# AFE_32_SUP.net
KiCad netlist of a schematic drawn in Altium Designer
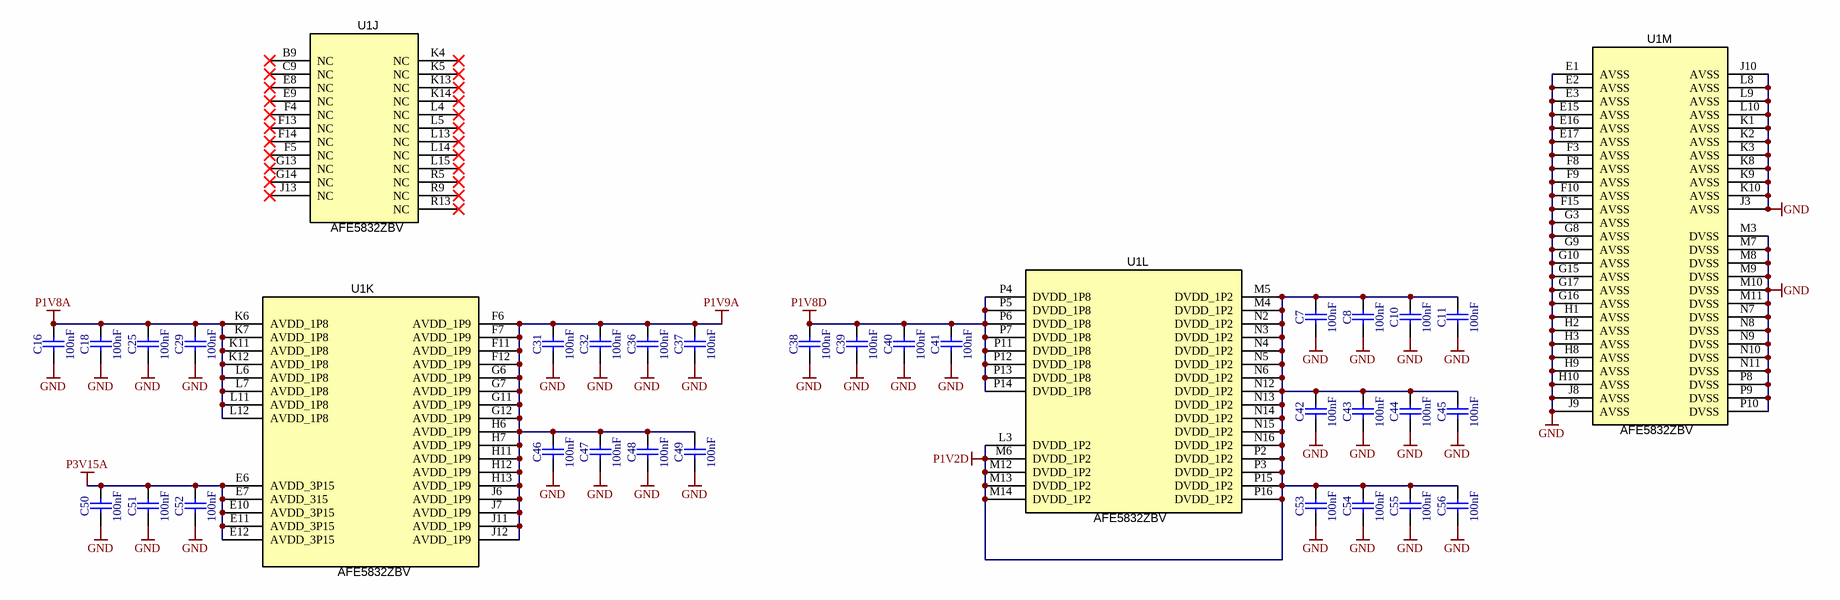
[diagram p0: AFE_32_SUP.SchDoc]

(export (version "E")
  (design (tool "Eeschema 10.0.6"))
  (components
    (comp (ref "C7")
      (value "100nF")
      (footprint "CAPC0603X33N")
      (description "Non-polarised capacitor")
      (fields
        (field (name "PART NUMBER") "CC0201_100NF_6.3V_10%_X7R")
        (field (name "VOLTAGE") "6.3V")
        (field (name "AUTHOR") "CERN DEM BC")
      )
      (libsource (lib "Capacitors") (part "Capacitor - non polarized"))
    )
    (comp (ref "C8")
      (value "100nF")
      (footprint "CAPC0603X33N")
      (description "Non-polarised capacitor")
      (fields
        (field (name "PART NUMBER") "CC0201_100NF_6.3V_10%_X7R")
        (field (name "VOLTAGE") "6.3V")
        (field (name "AUTHOR") "CERN DEM BC")
      )
      (libsource (lib "Capacitors") (part "Capacitor - non polarized"))
    )
    (comp (ref "C10")
      (value "100nF")
      (footprint "CAPC0603X33N")
      (description "Non-polarised capacitor")
      (fields
        (field (name "PART NUMBER") "CC0201_100NF_6.3V_10%_X7R")
        (field (name "VOLTAGE") "6.3V")
        (field (name "AUTHOR") "CERN DEM BC")
      )
      (libsource (lib "Capacitors") (part "Capacitor - non polarized"))
    )
    (comp (ref "C11")
      (value "100nF")
      (footprint "CAPC0603X33N")
      (description "Non-polarised capacitor")
      (fields
        (field (name "PART NUMBER") "CC0201_100NF_6.3V_10%_X7R")
        (field (name "VOLTAGE") "6.3V")
        (field (name "AUTHOR") "CERN DEM BC")
      )
      (libsource (lib "Capacitors") (part "Capacitor - non polarized"))
    )
    (comp (ref "C16")
      (value "100nF")
      (footprint "CAPC0603X33N")
      (description "Non-polarised capacitor")
      (fields
        (field (name "PART NUMBER") "CC0201_100NF_6.3V_10%_X7R")
        (field (name "VOLTAGE") "6.3V")
        (field (name "AUTHOR") "CERN DEM BC")
      )
      (libsource (lib "Capacitors") (part "Capacitor - non polarized"))
    )
    (comp (ref "C18")
      (value "100nF")
      (footprint "CAPC0603X33N")
      (description "Non-polarised capacitor")
      (fields
        (field (name "PART NUMBER") "CC0201_100NF_6.3V_10%_X7R")
        (field (name "VOLTAGE") "6.3V")
        (field (name "AUTHOR") "CERN DEM BC")
      )
      (libsource (lib "Capacitors") (part "Capacitor - non polarized"))
    )
    (comp (ref "C25")
      (value "100nF")
      (footprint "CAPC0603X33N")
      (description "Non-polarised capacitor")
      (fields
        (field (name "PART NUMBER") "CC0201_100NF_6.3V_10%_X7R")
        (field (name "VOLTAGE") "6.3V")
        (field (name "AUTHOR") "CERN DEM BC")
      )
      (libsource (lib "Capacitors") (part "Capacitor - non polarized"))
    )
    (comp (ref "C29")
      (value "100nF")
      (footprint "CAPC0603X33N")
      (description "Non-polarised capacitor")
      (fields
        (field (name "PART NUMBER") "CC0201_100NF_6.3V_10%_X7R")
        (field (name "VOLTAGE") "6.3V")
        (field (name "AUTHOR") "CERN DEM BC")
      )
      (libsource (lib "Capacitors") (part "Capacitor - non polarized"))
    )
    (comp (ref "C31")
      (value "100nF")
      (footprint "CAPC0603X33N")
      (description "Non-polarised capacitor")
      (fields
        (field (name "PART NUMBER") "CC0201_100NF_6.3V_10%_X7R")
        (field (name "VOLTAGE") "6.3V")
        (field (name "AUTHOR") "CERN DEM BC")
      )
      (libsource (lib "Capacitors") (part "Capacitor - non polarized"))
    )
    (comp (ref "C32")
      (value "100nF")
      (footprint "CAPC0603X33N")
      (description "Non-polarised capacitor")
      (fields
        (field (name "PART NUMBER") "CC0201_100NF_6.3V_10%_X7R")
        (field (name "VOLTAGE") "6.3V")
        (field (name "AUTHOR") "CERN DEM BC")
      )
      (libsource (lib "Capacitors") (part "Capacitor - non polarized"))
    )
    (comp (ref "C36")
      (value "100nF")
      (footprint "CAPC0603X33N")
      (description "Non-polarised capacitor")
      (fields
        (field (name "PART NUMBER") "CC0201_100NF_6.3V_10%_X7R")
        (field (name "VOLTAGE") "6.3V")
        (field (name "AUTHOR") "CERN DEM BC")
      )
      (libsource (lib "Capacitors") (part "Capacitor - non polarized"))
    )
    (comp (ref "C37")
      (value "100nF")
      (footprint "CAPC0603X33N")
      (description "Non-polarised capacitor")
      (fields
        (field (name "PART NUMBER") "CC0201_100NF_6.3V_10%_X7R")
        (field (name "VOLTAGE") "6.3V")
        (field (name "AUTHOR") "CERN DEM BC")
      )
      (libsource (lib "Capacitors") (part "Capacitor - non polarized"))
    )
    (comp (ref "C38")
      (value "100nF")
      (footprint "CAPC0603X33N")
      (description "Non-polarised capacitor")
      (fields
        (field (name "PART NUMBER") "CC0201_100NF_6.3V_10%_X7R")
        (field (name "VOLTAGE") "6.3V")
        (field (name "AUTHOR") "CERN DEM BC")
      )
      (libsource (lib "Capacitors") (part "Capacitor - non polarized"))
    )
    (comp (ref "C39")
      (value "100nF")
      (footprint "CAPC0603X33N")
      (description "Non-polarised capacitor")
      (fields
        (field (name "PART NUMBER") "CC0201_100NF_6.3V_10%_X7R")
        (field (name "VOLTAGE") "6.3V")
        (field (name "AUTHOR") "CERN DEM BC")
      )
      (libsource (lib "Capacitors") (part "Capacitor - non polarized"))
    )
    (comp (ref "C40")
      (value "100nF")
      (footprint "CAPC0603X33N")
      (description "Non-polarised capacitor")
      (fields
        (field (name "PART NUMBER") "CC0201_100NF_6.3V_10%_X7R")
        (field (name "VOLTAGE") "6.3V")
        (field (name "AUTHOR") "CERN DEM BC")
      )
      (libsource (lib "Capacitors") (part "Capacitor - non polarized"))
    )
    (comp (ref "C41")
      (value "100nF")
      (footprint "CAPC0603X33N")
      (description "Non-polarised capacitor")
      (fields
        (field (name "PART NUMBER") "CC0201_100NF_6.3V_10%_X7R")
        (field (name "VOLTAGE") "6.3V")
        (field (name "AUTHOR") "CERN DEM BC")
      )
      (libsource (lib "Capacitors") (part "Capacitor - non polarized"))
    )
    (comp (ref "C42")
      (value "100nF")
      (footprint "CAPC0603X33N")
      (description "Non-polarised capacitor")
      (fields
        (field (name "PART NUMBER") "CC0201_100NF_6.3V_10%_X7R")
        (field (name "VOLTAGE") "6.3V")
        (field (name "AUTHOR") "CERN DEM BC")
      )
      (libsource (lib "Capacitors") (part "Capacitor - non polarized"))
    )
    (comp (ref "C43")
      (value "100nF")
      (footprint "CAPC0603X33N")
      (description "Non-polarised capacitor")
      (fields
        (field (name "PART NUMBER") "CC0201_100NF_6.3V_10%_X7R")
        (field (name "VOLTAGE") "6.3V")
        (field (name "AUTHOR") "CERN DEM BC")
      )
      (libsource (lib "Capacitors") (part "Capacitor - non polarized"))
    )
    (comp (ref "C44")
      (value "100nF")
      (footprint "CAPC0603X33N")
      (description "Non-polarised capacitor")
      (fields
        (field (name "PART NUMBER") "CC0201_100NF_6.3V_10%_X7R")
        (field (name "VOLTAGE") "6.3V")
        (field (name "AUTHOR") "CERN DEM BC")
      )
      (libsource (lib "Capacitors") (part "Capacitor - non polarized"))
    )
    (comp (ref "C45")
      (value "100nF")
      (footprint "CAPC0603X33N")
      (description "Non-polarised capacitor")
      (fields
        (field (name "PART NUMBER") "CC0201_100NF_6.3V_10%_X7R")
        (field (name "VOLTAGE") "6.3V")
        (field (name "AUTHOR") "CERN DEM BC")
      )
      (libsource (lib "Capacitors") (part "Capacitor - non polarized"))
    )
    (comp (ref "C46")
      (value "100nF")
      (footprint "CAPC0603X33N")
      (description "Non-polarised capacitor")
      (fields
        (field (name "PART NUMBER") "CC0201_100NF_6.3V_10%_X7R")
        (field (name "VOLTAGE") "6.3V")
        (field (name "AUTHOR") "CERN DEM BC")
      )
      (libsource (lib "Capacitors") (part "Capacitor - non polarized"))
    )
    (comp (ref "C47")
      (value "100nF")
      (footprint "CAPC0603X33N")
      (description "Non-polarised capacitor")
      (fields
        (field (name "PART NUMBER") "CC0201_100NF_6.3V_10%_X7R")
        (field (name "VOLTAGE") "6.3V")
        (field (name "AUTHOR") "CERN DEM BC")
      )
      (libsource (lib "Capacitors") (part "Capacitor - non polarized"))
    )
    (comp (ref "C48")
      (value "100nF")
      (footprint "CAPC0603X33N")
      (description "Non-polarised capacitor")
      (fields
        (field (name "PART NUMBER") "CC0201_100NF_6.3V_10%_X7R")
        (field (name "VOLTAGE") "6.3V")
        (field (name "AUTHOR") "CERN DEM BC")
      )
      (libsource (lib "Capacitors") (part "Capacitor - non polarized"))
    )
    (comp (ref "C49")
      (value "100nF")
      (footprint "CAPC0603X33N")
      (description "Non-polarised capacitor")
      (fields
        (field (name "PART NUMBER") "CC0201_100NF_6.3V_10%_X7R")
        (field (name "VOLTAGE") "6.3V")
        (field (name "AUTHOR") "CERN DEM BC")
      )
      (libsource (lib "Capacitors") (part "Capacitor - non polarized"))
    )
    (comp (ref "C50")
      (value "100nF")
      (footprint "CAPC0603X33N")
      (description "Non-polarised capacitor")
      (fields
        (field (name "PART NUMBER") "CC0201_100NF_6.3V_10%_X7R")
        (field (name "VOLTAGE") "6.3V")
        (field (name "AUTHOR") "CERN DEM BC")
      )
      (libsource (lib "Capacitors") (part "Capacitor - non polarized"))
    )
    (comp (ref "C51")
      (value "100nF")
      (footprint "CAPC0603X33N")
      (description "Non-polarised capacitor")
      (fields
        (field (name "PART NUMBER") "CC0201_100NF_6.3V_10%_X7R")
        (field (name "VOLTAGE") "6.3V")
        (field (name "AUTHOR") "CERN DEM BC")
      )
      (libsource (lib "Capacitors") (part "Capacitor - non polarized"))
    )
    (comp (ref "C52")
      (value "100nF")
      (footprint "CAPC0603X33N")
      (description "Non-polarised capacitor")
      (fields
        (field (name "PART NUMBER") "CC0201_100NF_6.3V_10%_X7R")
        (field (name "VOLTAGE") "6.3V")
        (field (name "AUTHOR") "CERN DEM BC")
      )
      (libsource (lib "Capacitors") (part "Capacitor - non polarized"))
    )
    (comp (ref "C53")
      (value "100nF")
      (footprint "CAPC0603X33N")
      (description "Non-polarised capacitor")
      (fields
        (field (name "PART NUMBER") "CC0201_100NF_6.3V_10%_X7R")
        (field (name "VOLTAGE") "6.3V")
        (field (name "AUTHOR") "CERN DEM BC")
      )
      (libsource (lib "Capacitors") (part "Capacitor - non polarized"))
    )
    (comp (ref "C54")
      (value "100nF")
      (footprint "CAPC0603X33N")
      (description "Non-polarised capacitor")
      (fields
        (field (name "PART NUMBER") "CC0201_100NF_6.3V_10%_X7R")
        (field (name "VOLTAGE") "6.3V")
        (field (name "AUTHOR") "CERN DEM BC")
      )
      (libsource (lib "Capacitors") (part "Capacitor - non polarized"))
    )
    (comp (ref "C55")
      (value "100nF")
      (footprint "CAPC0603X33N")
      (description "Non-polarised capacitor")
      (fields
        (field (name "PART NUMBER") "CC0201_100NF_6.3V_10%_X7R")
        (field (name "VOLTAGE") "6.3V")
        (field (name "AUTHOR") "CERN DEM BC")
      )
      (libsource (lib "Capacitors") (part "Capacitor - non polarized"))
    )
    (comp (ref "C56")
      (value "100nF")
      (footprint "CAPC0603X33N")
      (description "Non-polarised capacitor")
      (fields
        (field (name "PART NUMBER") "CC0201_100NF_6.3V_10%_X7R")
        (field (name "VOLTAGE") "6.3V")
        (field (name "AUTHOR") "CERN DEM BC")
      )
      (libsource (lib "Capacitors") (part "Capacitor - non polarized"))
    )
    (comp (ref "U1")
      (value "AFE5832ZBV")
      (footprint "BGA289C80P17X17_1500X1500X140")
      (fields
        (field (name "MANUFACTURER") "Texas Instruments")
        (field (name "SYMBOLCREATOR") "Altium")
        (field (name "PUBLISHER") "Texas Instruments")
      )
      (libsource (lib "TI_Pre_RTM") (part "AFE58JD32ZBV"))
    )
  )
  (nets
    (net (code "1") (name "GND") (class "Default")
      (node (ref "C10") (pin "1") (pinfunction "1_1") (pintype "passive"))
      (node (ref "C11") (pin "1") (pinfunction "1_1") (pintype "passive"))
      (node (ref "C16") (pin "1") (pinfunction "1_1") (pintype "passive"))
      (node (ref "C18") (pin "1") (pinfunction "1_1") (pintype "passive"))
      (node (ref "C25") (pin "1") (pinfunction "1_1") (pintype "passive"))
      (node (ref "C29") (pin "1") (pinfunction "1_1") (pintype "passive"))
      (node (ref "C31") (pin "1") (pinfunction "1_1") (pintype "passive"))
      (node (ref "C32") (pin "1") (pinfunction "1_1") (pintype "passive"))
      (node (ref "C36") (pin "1") (pinfunction "1_1") (pintype "passive"))
      (node (ref "C37") (pin "1") (pinfunction "1_1") (pintype "passive"))
      (node (ref "C38") (pin "1") (pinfunction "1_1") (pintype "passive"))
      (node (ref "C39") (pin "1") (pinfunction "1_1") (pintype "passive"))
      (node (ref "C40") (pin "1") (pinfunction "1_1") (pintype "passive"))
      (node (ref "C41") (pin "1") (pinfunction "1_1") (pintype "passive"))
      (node (ref "C42") (pin "1") (pinfunction "1_1") (pintype "passive"))
      (node (ref "C43") (pin "1") (pinfunction "1_1") (pintype "passive"))
      (node (ref "C44") (pin "1") (pinfunction "1_1") (pintype "passive"))
      (node (ref "C45") (pin "1") (pinfunction "1_1") (pintype "passive"))
      (node (ref "C46") (pin "1") (pinfunction "1_1") (pintype "passive"))
      (node (ref "C47") (pin "1") (pinfunction "1_1") (pintype "passive"))
      (node (ref "C48") (pin "1") (pinfunction "1_1") (pintype "passive"))
      (node (ref "C49") (pin "1") (pinfunction "1_1") (pintype "passive"))
      (node (ref "C50") (pin "1") (pinfunction "1_1") (pintype "passive"))
      (node (ref "C51") (pin "1") (pinfunction "1_1") (pintype "passive"))
      (node (ref "C52") (pin "1") (pinfunction "1_1") (pintype "passive"))
      (node (ref "C53") (pin "1") (pinfunction "1_1") (pintype "passive"))
      (node (ref "C54") (pin "1") (pinfunction "1_1") (pintype "passive"))
      (node (ref "C55") (pin "1") (pinfunction "1_1") (pintype "passive"))
      (node (ref "C56") (pin "1") (pinfunction "1_1") (pintype "passive"))
      (node (ref "C7") (pin "1") (pinfunction "1_1") (pintype "passive"))
      (node (ref "C8") (pin "1") (pinfunction "1_1") (pintype "passive"))
      (node (ref "U1") (pin "E1") (pinfunction "AVSS_E1") (pintype "power_in"))
      (node (ref "U1") (pin "E15") (pinfunction "AVSS_E15") (pintype "power_in"))
      (node (ref "U1") (pin "E16") (pinfunction "AVSS_E16") (pintype "power_in"))
      (node (ref "U1") (pin "E17") (pinfunction "AVSS_E17") (pintype "power_in"))
      (node (ref "U1") (pin "E2") (pinfunction "AVSS_E2") (pintype "power_in"))
      (node (ref "U1") (pin "E3") (pinfunction "AVSS_E3") (pintype "power_in"))
      (node (ref "U1") (pin "F10") (pinfunction "AVSS_F10") (pintype "power_in"))
      (node (ref "U1") (pin "F15") (pinfunction "AVSS_F15") (pintype "power_in"))
      (node (ref "U1") (pin "F3") (pinfunction "AVSS_F3") (pintype "power_in"))
      (node (ref "U1") (pin "F8") (pinfunction "AVSS_F8") (pintype "power_in"))
      (node (ref "U1") (pin "F9") (pinfunction "AVSS_F9") (pintype "power_in"))
      (node (ref "U1") (pin "G10") (pinfunction "AVSS_G10") (pintype "power_in"))
      (node (ref "U1") (pin "G15") (pinfunction "AVSS_G15") (pintype "power_in"))
      (node (ref "U1") (pin "G16") (pinfunction "AVSS_G16") (pintype "power_in"))
      (node (ref "U1") (pin "G17") (pinfunction "AVSS_G17") (pintype "power_in"))
      (node (ref "U1") (pin "G3") (pinfunction "AVSS_G3") (pintype "power_in"))
      (node (ref "U1") (pin "G8") (pinfunction "AVSS_G8") (pintype "power_in"))
      (node (ref "U1") (pin "G9") (pinfunction "AVSS_G9") (pintype "power_in"))
      (node (ref "U1") (pin "H1") (pinfunction "AVSS_H1") (pintype "power_in"))
      (node (ref "U1") (pin "H10") (pinfunction "AVSS_H10") (pintype "power_in"))
      (node (ref "U1") (pin "H2") (pinfunction "AVSS_H2") (pintype "power_in"))
      (node (ref "U1") (pin "H3") (pinfunction "AVSS_H3") (pintype "power_in"))
      (node (ref "U1") (pin "H8") (pinfunction "AVSS_H8") (pintype "power_in"))
      (node (ref "U1") (pin "H9") (pinfunction "AVSS_H9") (pintype "power_in"))
      (node (ref "U1") (pin "J10") (pinfunction "AVSS_J10") (pintype "power_in"))
      (node (ref "U1") (pin "J3") (pinfunction "AVSS_J3") (pintype "power_in"))
      (node (ref "U1") (pin "J8") (pinfunction "AVSS_J8") (pintype "power_in"))
      (node (ref "U1") (pin "J9") (pinfunction "AVSS_J9") (pintype "power_in"))
      (node (ref "U1") (pin "K1") (pinfunction "AVSS_K1") (pintype "power_in"))
      (node (ref "U1") (pin "K10") (pinfunction "AVSS_K10") (pintype "power_in"))
      (node (ref "U1") (pin "K2") (pinfunction "AVSS_K2") (pintype "power_in"))
      (node (ref "U1") (pin "K3") (pinfunction "AVSS_K3") (pintype "power_in"))
      (node (ref "U1") (pin "K8") (pinfunction "AVSS_K8") (pintype "power_in"))
      (node (ref "U1") (pin "K9") (pinfunction "AVSS_K9") (pintype "power_in"))
      (node (ref "U1") (pin "L10") (pinfunction "AVSS_L10") (pintype "power_in"))
      (node (ref "U1") (pin "L8") (pinfunction "AVSS_L8") (pintype "power_in"))
      (node (ref "U1") (pin "L9") (pinfunction "AVSS_L9") (pintype "power_in"))
      (node (ref "U1") (pin "M10") (pinfunction "DVSS_M10") (pintype "power_in"))
      (node (ref "U1") (pin "M11") (pinfunction "DVSS_M11") (pintype "power_in"))
      (node (ref "U1") (pin "M3") (pinfunction "DVSS_M3") (pintype "power_in"))
      (node (ref "U1") (pin "M7") (pinfunction "DVSS_M7") (pintype "power_in"))
      (node (ref "U1") (pin "M8") (pinfunction "DVSS_M8") (pintype "power_in"))
      (node (ref "U1") (pin "M9") (pinfunction "DVSS_M9") (pintype "power_in"))
      (node (ref "U1") (pin "N10") (pinfunction "DVSS_N10") (pintype "power_in"))
      (node (ref "U1") (pin "N11") (pinfunction "DVSS_N11") (pintype "power_in"))
      (node (ref "U1") (pin "N7") (pinfunction "DVSS_N7") (pintype "power_in"))
      (node (ref "U1") (pin "N8") (pinfunction "DVSS_N8") (pintype "power_in"))
      (node (ref "U1") (pin "N9") (pinfunction "DVSS_N9") (pintype "power_in"))
      (node (ref "U1") (pin "P10") (pinfunction "DVSS_P10") (pintype "power_in"))
      (node (ref "U1") (pin "P8") (pinfunction "DVSS_P8") (pintype "power_in"))
      (node (ref "U1") (pin "P9") (pinfunction "DVSS_P9") (pintype "power_in"))
    )
    (net (code "2") (name "P1V2D") (class "Default")
      (node (ref "C10") (pin "2") (pinfunction "2_2") (pintype "passive"))
      (node (ref "C11") (pin "2") (pinfunction "2_2") (pintype "passive"))
      (node (ref "C42") (pin "2") (pinfunction "2_2") (pintype "passive"))
      (node (ref "C43") (pin "2") (pinfunction "2_2") (pintype "passive"))
      (node (ref "C44") (pin "2") (pinfunction "2_2") (pintype "passive"))
      (node (ref "C45") (pin "2") (pinfunction "2_2") (pintype "passive"))
      (node (ref "C53") (pin "2") (pinfunction "2_2") (pintype "passive"))
      (node (ref "C54") (pin "2") (pinfunction "2_2") (pintype "passive"))
      (node (ref "C55") (pin "2") (pinfunction "2_2") (pintype "passive"))
      (node (ref "C56") (pin "2") (pinfunction "2_2") (pintype "passive"))
      (node (ref "C7") (pin "2") (pinfunction "2_2") (pintype "passive"))
      (node (ref "C8") (pin "2") (pinfunction "2_2") (pintype "passive"))
      (node (ref "U1") (pin "L3") (pinfunction "DVDD_1P2_L3") (pintype "power_in"))
      (node (ref "U1") (pin "M12") (pinfunction "DVDD_1P2_M12") (pintype "power_in"))
      (node (ref "U1") (pin "M13") (pinfunction "DVDD_1P2_M13") (pintype "power_in"))
      (node (ref "U1") (pin "M14") (pinfunction "DVDD_1P2_M14") (pintype "power_in"))
      (node (ref "U1") (pin "M4") (pinfunction "DVDD_1P2_M4") (pintype "power_in"))
      (node (ref "U1") (pin "M5") (pinfunction "DVDD_1P2_M5") (pintype "power_in"))
      (node (ref "U1") (pin "M6") (pinfunction "DVDD_1P2_M6") (pintype "power_in"))
      (node (ref "U1") (pin "N12") (pinfunction "DVDD_1P2_N12") (pintype "power_in"))
      (node (ref "U1") (pin "N13") (pinfunction "DVDD_1P2_N13") (pintype "power_in"))
      (node (ref "U1") (pin "N14") (pinfunction "DVDD_1P2_N14") (pintype "power_in"))
      (node (ref "U1") (pin "N15") (pinfunction "DVDD_1P2_N15") (pintype "power_in"))
      (node (ref "U1") (pin "N16") (pinfunction "DVDD_1P2_N16") (pintype "power_in"))
      (node (ref "U1") (pin "N2") (pinfunction "DVDD_1P2_N2") (pintype "power_in"))
      (node (ref "U1") (pin "N3") (pinfunction "DVDD_1P2_N3") (pintype "power_in"))
      (node (ref "U1") (pin "N4") (pinfunction "DVDD_1P2_N4") (pintype "power_in"))
      (node (ref "U1") (pin "N5") (pinfunction "DVDD_1P2_N5") (pintype "power_in"))
      (node (ref "U1") (pin "N6") (pinfunction "DVDD_1P2_N6") (pintype "power_in"))
      (node (ref "U1") (pin "P15") (pinfunction "DVDD_1P2_P15") (pintype "power_in"))
      (node (ref "U1") (pin "P16") (pinfunction "DVDD_1P2_P16") (pintype "power_in"))
      (node (ref "U1") (pin "P2") (pinfunction "DVDD_1P2_P2") (pintype "power_in"))
      (node (ref "U1") (pin "P3") (pinfunction "DVDD_1P2_P3") (pintype "power_in"))
    )
    (net (code "3") (name "P1V8A") (class "Default")
      (node (ref "C16") (pin "2") (pinfunction "2_2") (pintype "passive"))
      (node (ref "C18") (pin "2") (pinfunction "2_2") (pintype "passive"))
      (node (ref "C25") (pin "2") (pinfunction "2_2") (pintype "passive"))
      (node (ref "C29") (pin "2") (pinfunction "2_2") (pintype "passive"))
      (node (ref "U1") (pin "K11") (pinfunction "AVDD_1P8_K11") (pintype "power_in"))
      (node (ref "U1") (pin "K12") (pinfunction "AVDD_1P8_K12") (pintype "power_in"))
      (node (ref "U1") (pin "K6") (pinfunction "AVDD_1P8_K6") (pintype "power_in"))
      (node (ref "U1") (pin "K7") (pinfunction "AVDD_1P8_K7") (pintype "power_in"))
      (node (ref "U1") (pin "L11") (pinfunction "AVDD_1P8_L11") (pintype "power_in"))
      (node (ref "U1") (pin "L12") (pinfunction "AVDD_1P8_L12") (pintype "power_in"))
      (node (ref "U1") (pin "L6") (pinfunction "AVDD_1P8_L6") (pintype "power_in"))
      (node (ref "U1") (pin "L7") (pinfunction "AVDD_1P8_L7") (pintype "power_in"))
    )
    (net (code "4") (name "P1V8D") (class "Default")
      (node (ref "C38") (pin "2") (pinfunction "2_2") (pintype "passive"))
      (node (ref "C39") (pin "2") (pinfunction "2_2") (pintype "passive"))
      (node (ref "C40") (pin "2") (pinfunction "2_2") (pintype "passive"))
      (node (ref "C41") (pin "2") (pinfunction "2_2") (pintype "passive"))
      (node (ref "U1") (pin "P11") (pinfunction "DVDD_1P8_P11") (pintype "power_in"))
      (node (ref "U1") (pin "P12") (pinfunction "DVDD_1P8_P12") (pintype "power_in"))
      (node (ref "U1") (pin "P13") (pinfunction "DVDD_1P8_P13") (pintype "power_in"))
      (node (ref "U1") (pin "P14") (pinfunction "DVDD_1P8_P14") (pintype "power_in"))
      (node (ref "U1") (pin "P4") (pinfunction "DVDD_1P8_P4") (pintype "power_in"))
      (node (ref "U1") (pin "P5") (pinfunction "DVDD_1P8_P5") (pintype "power_in"))
      (node (ref "U1") (pin "P6") (pinfunction "DVDD_1P8_P6") (pintype "power_in"))
      (node (ref "U1") (pin "P7") (pinfunction "DVDD_1P8_P7") (pintype "power_in"))
    )
    (net (code "5") (name "P1V9A") (class "Default")
      (node (ref "C31") (pin "2") (pinfunction "2_2") (pintype "passive"))
      (node (ref "C32") (pin "2") (pinfunction "2_2") (pintype "passive"))
      (node (ref "C36") (pin "2") (pinfunction "2_2") (pintype "passive"))
      (node (ref "C37") (pin "2") (pinfunction "2_2") (pintype "passive"))
      (node (ref "C46") (pin "2") (pinfunction "2_2") (pintype "passive"))
      (node (ref "C47") (pin "2") (pinfunction "2_2") (pintype "passive"))
      (node (ref "C48") (pin "2") (pinfunction "2_2") (pintype "passive"))
      (node (ref "C49") (pin "2") (pinfunction "2_2") (pintype "passive"))
      (node (ref "U1") (pin "F11") (pinfunction "AVDD_1P9_F11") (pintype "power_in"))
      (node (ref "U1") (pin "F12") (pinfunction "AVDD_1P9_F12") (pintype "power_in"))
      (node (ref "U1") (pin "F6") (pinfunction "AVDD_1P9_F6") (pintype "power_in"))
      (node (ref "U1") (pin "F7") (pinfunction "AVDD_1P9_F7") (pintype "power_in"))
      (node (ref "U1") (pin "G11") (pinfunction "AVDD_1P9_G11") (pintype "power_in"))
      (node (ref "U1") (pin "G12") (pinfunction "AVDD_1P9_G12") (pintype "power_in"))
      (node (ref "U1") (pin "G6") (pinfunction "AVDD_1P9_G6") (pintype "power_in"))
      (node (ref "U1") (pin "G7") (pinfunction "AVDD_1P9_G7") (pintype "power_in"))
      (node (ref "U1") (pin "H11") (pinfunction "AVDD_1P9_H11") (pintype "power_in"))
      (node (ref "U1") (pin "H12") (pinfunction "AVDD_1P9_H12") (pintype "power_in"))
      (node (ref "U1") (pin "H13") (pinfunction "AVDD_1P9_H13") (pintype "power_in"))
      (node (ref "U1") (pin "H6") (pinfunction "AVDD_1P9_H6") (pintype "power_in"))
      (node (ref "U1") (pin "H7") (pinfunction "AVDD_1P9_H7") (pintype "power_in"))
      (node (ref "U1") (pin "J11") (pinfunction "AVDD_1P9_J11") (pintype "power_in"))
      (node (ref "U1") (pin "J12") (pinfunction "AVDD_1P9_J12") (pintype "power_in"))
      (node (ref "U1") (pin "J6") (pinfunction "AVDD_1P9_J6") (pintype "power_in"))
      (node (ref "U1") (pin "J7") (pinfunction "AVDD_1P9_J7") (pintype "power_in"))
    )
    (net (code "6") (name "P3V15A") (class "Default")
      (node (ref "C50") (pin "2") (pinfunction "2_2") (pintype "passive"))
      (node (ref "C51") (pin "2") (pinfunction "2_2") (pintype "passive"))
      (node (ref "C52") (pin "2") (pinfunction "2_2") (pintype "passive"))
      (node (ref "U1") (pin "E10") (pinfunction "AVDD_3P15_E10") (pintype "power_in"))
      (node (ref "U1") (pin "E11") (pinfunction "AVDD_3P15_E11") (pintype "power_in"))
      (node (ref "U1") (pin "E12") (pinfunction "AVDD_3P15_E12") (pintype "power_in"))
      (node (ref "U1") (pin "E6") (pinfunction "AVDD_3P15_E6") (pintype "power_in"))
      (node (ref "U1") (pin "E7") (pinfunction "AVDD_315_E7") (pintype "power_in"))
    )
    (net (code "7") (name "unconnected-(U1J-NC-PadB9)") (class "Default")
      (node (ref "U1") (pin "B9") (pinfunction "NC_B9") (pintype "passive+no_connect"))
    )
    (net (code "8") (name "unconnected-(U1J-NC-PadC9)") (class "Default")
      (node (ref "U1") (pin "C9") (pinfunction "NC_C9") (pintype "passive+no_connect"))
    )
    (net (code "9") (name "unconnected-(U1J-NC-PadE8)") (class "Default")
      (node (ref "U1") (pin "E8") (pinfunction "NC_E8") (pintype "passive+no_connect"))
    )
    (net (code "10") (name "unconnected-(U1J-NC-PadE9)") (class "Default")
      (node (ref "U1") (pin "E9") (pinfunction "NC_E9") (pintype "passive+no_connect"))
    )
    (net (code "11") (name "unconnected-(U1J-NC-PadF4)") (class "Default")
      (node (ref "U1") (pin "F4") (pinfunction "NC_F4") (pintype "passive+no_connect"))
    )
    (net (code "12") (name "unconnected-(U1J-NC-PadF5)") (class "Default")
      (node (ref "U1") (pin "F5") (pinfunction "NC_F5") (pintype "passive+no_connect"))
    )
    (net (code "13") (name "unconnected-(U1J-NC-PadF13)") (class "Default")
      (node (ref "U1") (pin "F13") (pinfunction "NC_F13") (pintype "passive+no_connect"))
    )
    (net (code "14") (name "unconnected-(U1J-NC-PadF14)") (class "Default")
      (node (ref "U1") (pin "F14") (pinfunction "NC_F14") (pintype "passive+no_connect"))
    )
    (net (code "15") (name "unconnected-(U1J-NC-PadG13)") (class "Default")
      (node (ref "U1") (pin "G13") (pinfunction "NC_G13") (pintype "passive+no_connect"))
    )
    (net (code "16") (name "unconnected-(U1J-NC-PadG14)") (class "Default")
      (node (ref "U1") (pin "G14") (pinfunction "NC_G14") (pintype "passive+no_connect"))
    )
    (net (code "17") (name "unconnected-(U1J-NC-PadJ13)") (class "Default")
      (node (ref "U1") (pin "J13") (pinfunction "NC_J13") (pintype "passive+no_connect"))
    )
    (net (code "18") (name "unconnected-(U1J-NC-PadK4)") (class "Default")
      (node (ref "U1") (pin "K4") (pinfunction "NC_K4") (pintype "passive+no_connect"))
    )
    (net (code "19") (name "unconnected-(U1J-NC-PadK5)") (class "Default")
      (node (ref "U1") (pin "K5") (pinfunction "NC_K5") (pintype "passive+no_connect"))
    )
    (net (code "20") (name "unconnected-(U1J-NC-PadK13)") (class "Default")
      (node (ref "U1") (pin "K13") (pinfunction "NC_K13") (pintype "passive+no_connect"))
    )
    (net (code "21") (name "unconnected-(U1J-NC-PadK14)") (class "Default")
      (node (ref "U1") (pin "K14") (pinfunction "NC_K14") (pintype "passive+no_connect"))
    )
    (net (code "22") (name "unconnected-(U1J-NC-PadL4)") (class "Default")
      (node (ref "U1") (pin "L4") (pinfunction "NC_L4") (pintype "passive+no_connect"))
    )
    (net (code "23") (name "unconnected-(U1J-NC-PadL5)") (class "Default")
      (node (ref "U1") (pin "L5") (pinfunction "NC_L5") (pintype "passive+no_connect"))
    )
    (net (code "24") (name "unconnected-(U1J-NC-PadL13)") (class "Default")
      (node (ref "U1") (pin "L13") (pinfunction "NC_L13") (pintype "passive+no_connect"))
    )
    (net (code "25") (name "unconnected-(U1J-NC-PadL14)") (class "Default")
      (node (ref "U1") (pin "L14") (pinfunction "NC_L14") (pintype "passive+no_connect"))
    )
    (net (code "26") (name "unconnected-(U1J-NC-PadL15)") (class "Default")
      (node (ref "U1") (pin "L15") (pinfunction "NC_L15") (pintype "passive+no_connect"))
    )
    (net (code "27") (name "unconnected-(U1J-NC-PadR5)") (class "Default")
      (node (ref "U1") (pin "R5") (pinfunction "NC_R5") (pintype "passive+no_connect"))
    )
    (net (code "28") (name "unconnected-(U1J-NC-PadR9)") (class "Default")
      (node (ref "U1") (pin "R9") (pinfunction "NC_R9") (pintype "passive+no_connect"))
    )
    (net (code "29") (name "unconnected-(U1J-NC-PadR13)") (class "Default")
      (node (ref "U1") (pin "R13") (pinfunction "NC_R13") (pintype "passive+no_connect"))
    )
  )
)
